# triac_driver.net
KiCad netlist of a schematic drawn in EAGLE
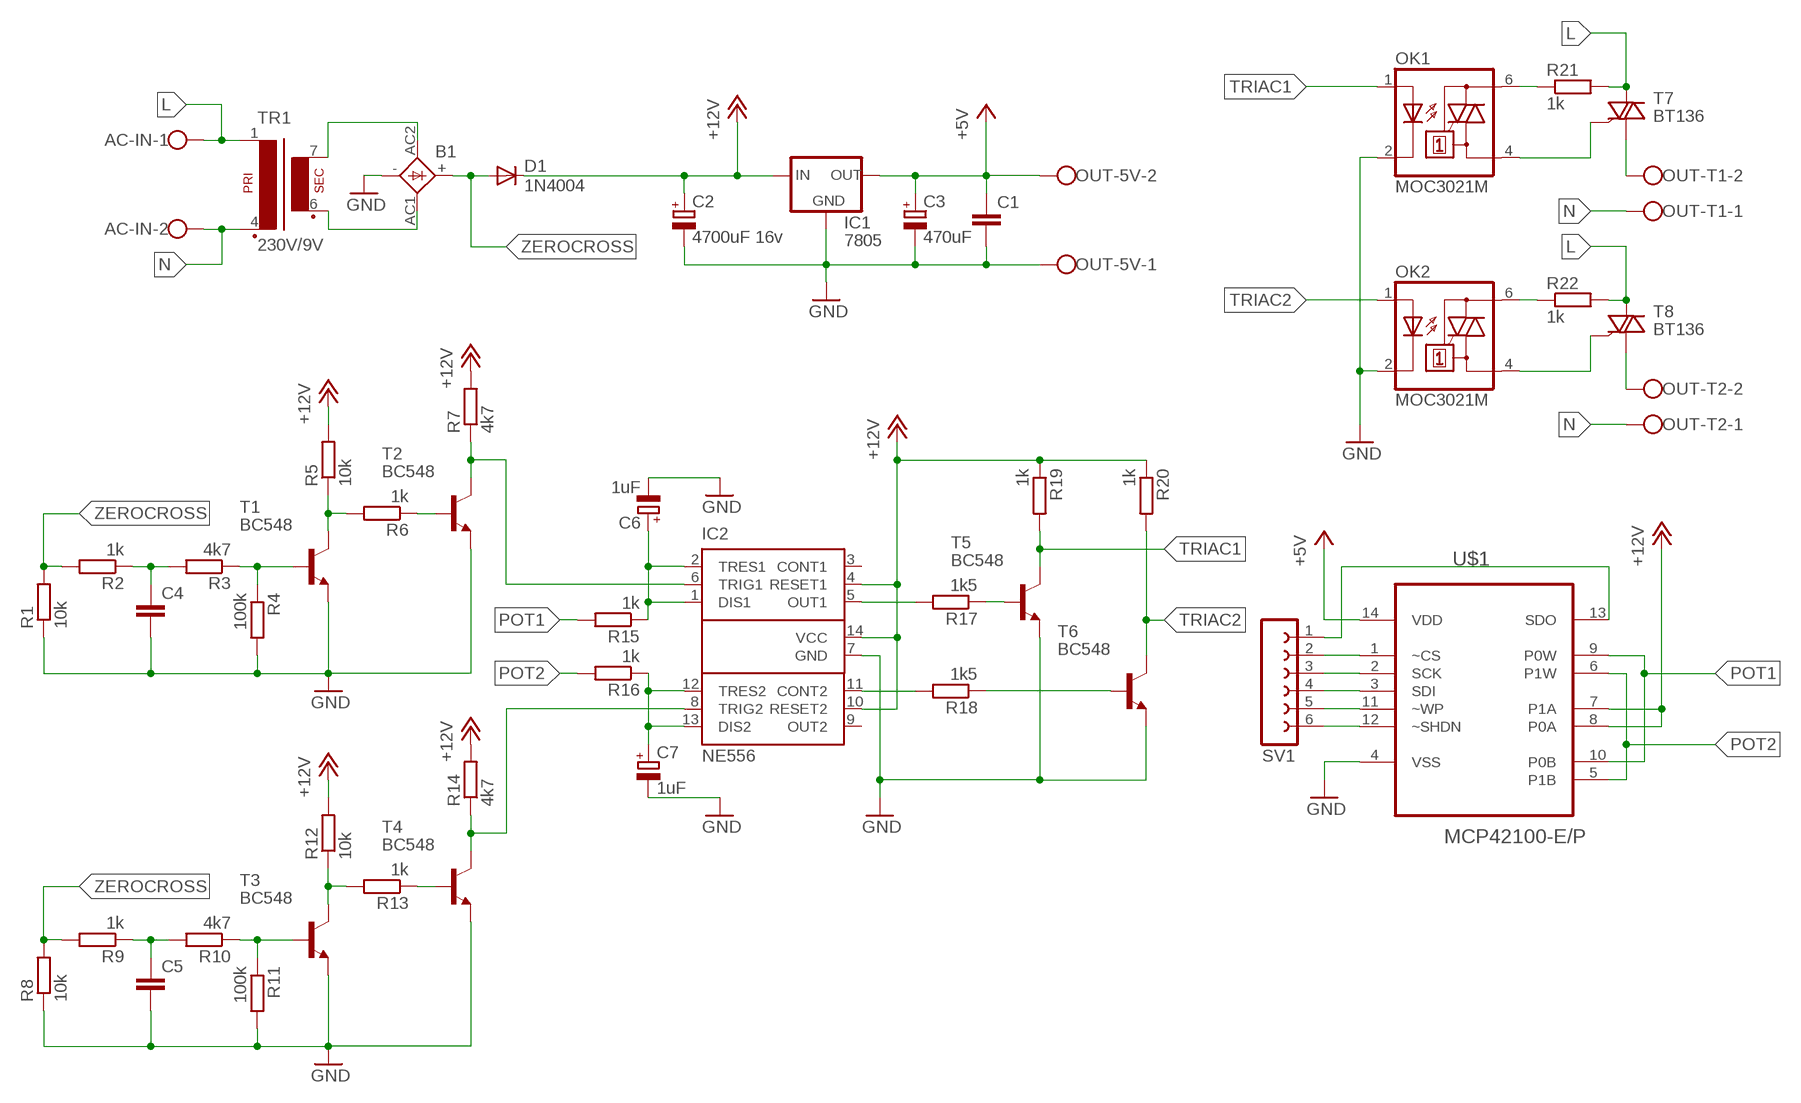
[diagram p0: schematic, sheet 1]

(export (version "E")
  (design (tool "Eeschema 10.0.6"))
  (components
    (comp (ref "AC-IN")
      (value "W237-102")
      (footprint "eagle-import:W237-102")
      (fields (field (name "MPN") "237-102"))
      (libsource (lib "eagle-import") (part "W237-102"))
    )
    (comp (ref "B1")
      (value "FBP1,5")
      (footprint "eagle-import:FBP1,5")
      (libsource (lib "eagle-import") (part "FBP1,5"))
    )
    (comp (ref "C1")
      (value "C-EU025-060X050")
      (footprint "eagle-import:C025-060X050")
      (libsource (lib "eagle-import") (part "C-EU025-060X050"))
    )
    (comp (ref "C2")
      (value "4700uF 16v")
      (footprint "eagle-import:E3,5-8")
      (libsource (lib "eagle-import") (part "CPOL-EUE3.5-8"))
    )
    (comp (ref "C3")
      (value "470uF")
      (footprint "eagle-import:E3,5-8")
      (libsource (lib "eagle-import") (part "CPOL-EUE3.5-8"))
    )
    (comp (ref "C4")
      (value "C-EU025-060X050")
      (footprint "eagle-import:C025-060X050")
      (libsource (lib "eagle-import") (part "C-EU025-060X050"))
    )
    (comp (ref "C5")
      (value "C-EU025-060X050")
      (footprint "eagle-import:C025-060X050")
      (libsource (lib "eagle-import") (part "C-EU025-060X050"))
    )
    (comp (ref "C6")
      (value "1uF")
      (footprint "eagle-import:E3,5-8")
      (libsource (lib "eagle-import") (part "CPOL-EUE3.5-8"))
    )
    (comp (ref "C7")
      (value "1uF")
      (footprint "eagle-import:E3,5-8")
      (libsource (lib "eagle-import") (part "CPOL-EUE3.5-8"))
    )
    (comp (ref "D1")
      (value "1N4004")
      (footprint "eagle-import:DO41-10")
      (libsource (lib "eagle-import") (part "1N4004"))
    )
    (comp (ref "IC1")
      (value "7805")
      (footprint "eagle-import:78LXX")
      (libsource (lib "eagle-import") (part "78LXX"))
    )
    (comp (ref "IC2")
      (value "NE556")
      (footprint "eagle-import:DIL14")
      (libsource (lib "eagle-import") (part "NE556"))
    )
    (comp (ref "OK1")
      (value "MOC3021M")
      (footprint "eagle-import:DIL06")
      (fields (field (name "MF") "FAIRCHILD SEMICONDUCTOR") (field (name "MPN") "MOC3021-M"))
      (libsource (lib "eagle-import") (part "MOC30M21"))
    )
    (comp (ref "OK2")
      (value "MOC3021M")
      (footprint "eagle-import:DIL06")
      (fields (field (name "MF") "FAIRCHILD SEMICONDUCTOR") (field (name "MPN") "MOC3021-M"))
      (libsource (lib "eagle-import") (part "MOC30M21"))
    )
    (comp (ref "OUT-5V")
      (value "W237-102")
      (footprint "eagle-import:W237-102")
      (fields (field (name "MPN") "237-102"))
      (libsource (lib "eagle-import") (part "W237-102"))
    )
    (comp (ref "OUT-T1")
      (value "W237-102")
      (footprint "eagle-import:W237-102")
      (fields (field (name "MPN") "237-102"))
      (libsource (lib "eagle-import") (part "W237-102"))
    )
    (comp (ref "OUT-T2")
      (value "W237-102")
      (footprint "eagle-import:W237-102")
      (fields (field (name "MPN") "237-102"))
      (libsource (lib "eagle-import") (part "W237-102"))
    )
    (comp (ref "R1")
      (value "10k")
      (footprint "eagle-import:0204_7")
      (libsource (lib "eagle-import") (part "R-EU_0204/7"))
    )
    (comp (ref "R2")
      (value "1k")
      (footprint "eagle-import:0204_7")
      (libsource (lib "eagle-import") (part "R-EU_0204/7"))
    )
    (comp (ref "R3")
      (value "4k7")
      (footprint "eagle-import:0204_7")
      (libsource (lib "eagle-import") (part "R-EU_0204/7"))
    )
    (comp (ref "R4")
      (value "100k")
      (footprint "eagle-import:0204_7")
      (libsource (lib "eagle-import") (part "R-EU_0204/7"))
    )
    (comp (ref "R5")
      (value "10k")
      (footprint "eagle-import:0204_7")
      (libsource (lib "eagle-import") (part "R-EU_0204/7"))
    )
    (comp (ref "R6")
      (value "1k")
      (footprint "eagle-import:0204_7")
      (libsource (lib "eagle-import") (part "R-EU_0204/7"))
    )
    (comp (ref "R7")
      (value "4k7")
      (footprint "eagle-import:0204_7")
      (libsource (lib "eagle-import") (part "R-EU_0204/7"))
    )
    (comp (ref "R8")
      (value "10k")
      (footprint "eagle-import:0204_7")
      (libsource (lib "eagle-import") (part "R-EU_0204/7"))
    )
    (comp (ref "R9")
      (value "1k")
      (footprint "eagle-import:0204_7")
      (libsource (lib "eagle-import") (part "R-EU_0204/7"))
    )
    (comp (ref "R10")
      (value "4k7")
      (footprint "eagle-import:0204_7")
      (libsource (lib "eagle-import") (part "R-EU_0204/7"))
    )
    (comp (ref "R11")
      (value "100k")
      (footprint "eagle-import:0204_7")
      (libsource (lib "eagle-import") (part "R-EU_0204/7"))
    )
    (comp (ref "R12")
      (value "10k")
      (footprint "eagle-import:0204_7")
      (libsource (lib "eagle-import") (part "R-EU_0204/7"))
    )
    (comp (ref "R13")
      (value "1k")
      (footprint "eagle-import:0204_7")
      (libsource (lib "eagle-import") (part "R-EU_0204/7"))
    )
    (comp (ref "R14")
      (value "4k7")
      (footprint "eagle-import:0204_7")
      (libsource (lib "eagle-import") (part "R-EU_0204/7"))
    )
    (comp (ref "R15")
      (value "1k")
      (footprint "eagle-import:0204_7")
      (libsource (lib "eagle-import") (part "R-EU_0204/7"))
    )
    (comp (ref "R16")
      (value "1k")
      (footprint "eagle-import:0204_7")
      (libsource (lib "eagle-import") (part "R-EU_0204/7"))
    )
    (comp (ref "R17")
      (value "1k5")
      (footprint "eagle-import:0204_7")
      (libsource (lib "eagle-import") (part "R-EU_0204/7"))
    )
    (comp (ref "R18")
      (value "1k5")
      (footprint "eagle-import:0204_7")
      (libsource (lib "eagle-import") (part "R-EU_0204/7"))
    )
    (comp (ref "R19")
      (value "1k")
      (footprint "eagle-import:0204_7")
      (libsource (lib "eagle-import") (part "R-EU_0204/7"))
    )
    (comp (ref "R20")
      (value "1k")
      (footprint "eagle-import:0204_7")
      (libsource (lib "eagle-import") (part "R-EU_0204/7"))
    )
    (comp (ref "R21")
      (value "1k")
      (footprint "eagle-import:0204_7")
      (libsource (lib "eagle-import") (part "R-EU_0204/7"))
    )
    (comp (ref "R22")
      (value "1k")
      (footprint "eagle-import:0204_7")
      (libsource (lib "eagle-import") (part "R-EU_0204/7"))
    )
    (comp (ref "SV1")
      (value "FE06-1")
      (footprint "eagle-import:FE06")
      (libsource (lib "eagle-import") (part "FE06-1"))
    )
    (comp (ref "T1")
      (value "BC548")
      (footprint "eagle-import:TO92")
      (libsource (lib "eagle-import") (part "BC547"))
    )
    (comp (ref "T2")
      (value "BC548")
      (footprint "eagle-import:TO92")
      (libsource (lib "eagle-import") (part "BC547"))
    )
    (comp (ref "T3")
      (value "BC548")
      (footprint "eagle-import:TO92")
      (libsource (lib "eagle-import") (part "BC547"))
    )
    (comp (ref "T4")
      (value "BC548")
      (footprint "eagle-import:TO92")
      (libsource (lib "eagle-import") (part "BC547"))
    )
    (comp (ref "T5")
      (value "BC548")
      (footprint "eagle-import:TO92")
      (libsource (lib "eagle-import") (part "BC547"))
    )
    (comp (ref "T6")
      (value "BC548")
      (footprint "eagle-import:TO92")
      (libsource (lib "eagle-import") (part "BC547"))
    )
    (comp (ref "T7")
      (value "BT136")
      (footprint "eagle-import:TO220AB")
      (libsource (lib "eagle-import") (part "BT136"))
    )
    (comp (ref "T8")
      (value "BT136")
      (footprint "eagle-import:TO220AB")
      (libsource (lib "eagle-import") (part "BT136"))
    )
    (comp (ref "TR1")
      (value "230V/9V")
      (footprint "eagle-import:EE20-1")
      (libsource (lib "eagle-import") (part "EE20-1"))
    )
    (comp (ref "U$1")
      (value "MCP42100-E/P")
      (footprint "eagle-import:DIP254P762X533-14")
      (fields (field (name "MPN") "MCP4241-103E/P"))
      (libsource (lib "eagle-import") (part "MCP4241-103E/P"))
    )
  )
  (nets
    (net (code "1") (name "+5V") (class "Default")
      (node (ref "C1") (pin "1") (pinfunction "1_1") (pintype "passive"))
      (node (ref "C3") (pin "+") (pinfunction "+_+") (pintype "passive"))
      (node (ref "IC1") (pin "OUT") (pinfunction "OUT_OUT") (pintype "passive"))
      (node (ref "OUT-5V") (pin "2") (pinfunction "KL_2") (pintype "passive"))
      (node (ref "U$1") (pin "14") (pinfunction "VDD_14") (pintype "power_in"))
    )
    (net (code "2") (name "+12V") (class "Default")
      (node (ref "C2") (pin "+") (pinfunction "+_+") (pintype "passive"))
      (node (ref "D1") (pin "C") (pinfunction "C_C") (pintype "passive"))
      (node (ref "IC1") (pin "IN") (pinfunction "IN_IN") (pintype "input"))
      (node (ref "IC2") (pin "10") (pinfunction "RESET2_10") (pintype "input"))
      (node (ref "IC2") (pin "14") (pinfunction "VCC_14") (pintype "power_in"))
      (node (ref "IC2") (pin "4") (pinfunction "RESET1_4") (pintype "input"))
      (node (ref "R12") (pin "2") (pinfunction "2_2") (pintype "passive"))
      (node (ref "R14") (pin "2") (pinfunction "2_2") (pintype "passive"))
      (node (ref "R19") (pin "1") (pinfunction "1_1") (pintype "passive"))
      (node (ref "R20") (pin "1") (pinfunction "1_1") (pintype "passive"))
      (node (ref "R5") (pin "2") (pinfunction "2_2") (pintype "passive"))
      (node (ref "R7") (pin "2") (pinfunction "2_2") (pintype "passive"))
      (node (ref "U$1") (pin "7") (pinfunction "P1A_7") (pintype "bidirectional"))
      (node (ref "U$1") (pin "8") (pinfunction "P0A_8") (pintype "bidirectional"))
    )
    (net (code "3") (name "GND") (class "Default")
      (node (ref "B1") (pin "-") (pinfunction "-_-") (pintype "passive"))
      (node (ref "C1") (pin "2") (pinfunction "2_2") (pintype "passive"))
      (node (ref "C2") (pin "-") (pinfunction "-_-") (pintype "passive"))
      (node (ref "C3") (pin "-") (pinfunction "-_-") (pintype "passive"))
      (node (ref "C4") (pin "2") (pinfunction "2_2") (pintype "passive"))
      (node (ref "C5") (pin "2") (pinfunction "2_2") (pintype "passive"))
      (node (ref "C6") (pin "-") (pinfunction "-_-") (pintype "passive"))
      (node (ref "C7") (pin "-") (pinfunction "-_-") (pintype "passive"))
      (node (ref "IC1") (pin "GND") (pinfunction "GND_GND") (pintype "input"))
      (node (ref "IC2") (pin "7") (pinfunction "GND_7") (pintype "power_in"))
      (node (ref "OK1") (pin "2") (pinfunction "C_2") (pintype "passive"))
      (node (ref "OK2") (pin "2") (pinfunction "C_2") (pintype "passive"))
      (node (ref "OUT-5V") (pin "1") (pinfunction "KL_1") (pintype "passive"))
      (node (ref "R1") (pin "1") (pinfunction "1_1") (pintype "passive"))
      (node (ref "R11") (pin "2") (pinfunction "2_2") (pintype "passive"))
      (node (ref "R4") (pin "2") (pinfunction "2_2") (pintype "passive"))
      (node (ref "R8") (pin "1") (pinfunction "1_1") (pintype "passive"))
      (node (ref "T1") (pin "1") (pinfunction "E_1") (pintype "passive"))
      (node (ref "T2") (pin "1") (pinfunction "E_1") (pintype "passive"))
      (node (ref "T3") (pin "1") (pinfunction "E_1") (pintype "passive"))
      (node (ref "T4") (pin "1") (pinfunction "E_1") (pintype "passive"))
      (node (ref "T5") (pin "1") (pinfunction "E_1") (pintype "passive"))
      (node (ref "T6") (pin "1") (pinfunction "E_1") (pintype "passive"))
      (node (ref "U$1") (pin "4") (pinfunction "VSS_4") (pintype "power_in"))
    )
    (net (code "4") (name "L") (class "Default")
      (node (ref "AC-IN") (pin "1") (pinfunction "KL_1") (pintype "passive"))
      (node (ref "R21") (pin "2") (pinfunction "2_2") (pintype "passive"))
      (node (ref "R22") (pin "2") (pinfunction "2_2") (pintype "passive"))
      (node (ref "T7") (pin "2") (pinfunction "A2_2") (pintype "passive"))
      (node (ref "T8") (pin "2") (pinfunction "A2_2") (pintype "passive"))
      (node (ref "TR1") (pin "1") (pinfunction "P1_1") (pintype "passive"))
    )
    (net (code "5") (name "N") (class "Default")
      (node (ref "AC-IN") (pin "2") (pinfunction "KL_2") (pintype "passive"))
      (node (ref "OUT-T1") (pin "1") (pinfunction "KL_1") (pintype "passive"))
      (node (ref "OUT-T2") (pin "1") (pinfunction "KL_1") (pintype "passive"))
      (node (ref "TR1") (pin "4") (pinfunction "P2_4") (pintype "passive"))
    )
    (net (code "6") (name "Net-(B1-AC1)") (class "Default")
      (node (ref "B1") (pin "AC2") (pinfunction "AC1_AC2") (pintype "passive"))
      (node (ref "TR1") (pin "7") (pinfunction "S4_7") (pintype "passive"))
    )
    (net (code "7") (name "Net-(B1-AC2)") (class "Default")
      (node (ref "B1") (pin "AC1") (pinfunction "AC2_AC1") (pintype "passive"))
      (node (ref "TR1") (pin "6") (pinfunction "S3_6") (pintype "passive"))
    )
    (net (code "8") (name "Net-(C4-Pad1)") (class "Default")
      (node (ref "C4") (pin "1") (pinfunction "1_1") (pintype "passive"))
      (node (ref "R2") (pin "1") (pinfunction "1_1") (pintype "passive"))
      (node (ref "R3") (pin "2") (pinfunction "2_2") (pintype "passive"))
    )
    (net (code "9") (name "Net-(C5-Pad1)") (class "Default")
      (node (ref "C5") (pin "1") (pinfunction "1_1") (pintype "passive"))
      (node (ref "R10") (pin "2") (pinfunction "2_2") (pintype "passive"))
      (node (ref "R9") (pin "1") (pinfunction "1_1") (pintype "passive"))
    )
    (net (code "10") (name "Net-(IC2-CONT2)") (class "Default")
      (node (ref "IC2") (pin "11") (pinfunction "CONT2_11") (pintype "input"))
      (node (ref "R18") (pin "2") (pinfunction "2_2") (pintype "passive"))
    )
    (net (code "11") (name "Net-(IC2-DIS1)") (class "Default")
      (node (ref "C6") (pin "+") (pinfunction "+_+") (pintype "passive"))
      (node (ref "IC2") (pin "1") (pinfunction "DIS1_1") (pintype "input"))
      (node (ref "IC2") (pin "2") (pinfunction "TRES1_2") (pintype "input"))
      (node (ref "R15") (pin "1") (pinfunction "1_1") (pintype "passive"))
    )
    (net (code "12") (name "Net-(IC2-DIS2)") (class "Default")
      (node (ref "C7") (pin "+") (pinfunction "+_+") (pintype "passive"))
      (node (ref "IC2") (pin "12") (pinfunction "TRES2_12") (pintype "input"))
      (node (ref "IC2") (pin "13") (pinfunction "DIS2_13") (pintype "input"))
      (node (ref "R16") (pin "1") (pinfunction "1_1") (pintype "passive"))
    )
    (net (code "13") (name "Net-(IC2-OUT1)") (class "Default")
      (node (ref "IC2") (pin "5") (pinfunction "OUT1_5") (pintype "output"))
      (node (ref "R17") (pin "2") (pinfunction "2_2") (pintype "passive"))
    )
    (net (code "14") (name "Net-(IC2-TRIG1)") (class "Default")
      (node (ref "IC2") (pin "6") (pinfunction "TRIG1_6") (pintype "input"))
      (node (ref "R7") (pin "1") (pinfunction "1_1") (pintype "passive"))
      (node (ref "T2") (pin "3") (pinfunction "C_3") (pintype "passive"))
    )
    (net (code "15") (name "Net-(IC2-TRIG2)") (class "Default")
      (node (ref "IC2") (pin "8") (pinfunction "TRIG2_8") (pintype "input"))
      (node (ref "R14") (pin "1") (pinfunction "1_1") (pintype "passive"))
      (node (ref "T4") (pin "3") (pinfunction "C_3") (pintype "passive"))
    )
    (net (code "16") (name "Net-(OK1-A1)") (class "Default")
      (node (ref "OK1") (pin "4") (pinfunction "A1_4") (pintype "passive"))
      (node (ref "T7") (pin "3") (pinfunction "G_3") (pintype "passive"))
    )
    (net (code "17") (name "Net-(OK1-A2)") (class "Default")
      (node (ref "OK1") (pin "6") (pinfunction "A2_6") (pintype "passive"))
      (node (ref "R21") (pin "1") (pinfunction "1_1") (pintype "passive"))
    )
    (net (code "18") (name "Net-(OK2-A1)") (class "Default")
      (node (ref "OK2") (pin "4") (pinfunction "A1_4") (pintype "passive"))
      (node (ref "T8") (pin "3") (pinfunction "G_3") (pintype "passive"))
    )
    (net (code "19") (name "Net-(OK2-A2)") (class "Default")
      (node (ref "OK2") (pin "6") (pinfunction "A2_6") (pintype "passive"))
      (node (ref "R22") (pin "1") (pinfunction "1_1") (pintype "passive"))
    )
    (net (code "20") (name "Net-(OUT-T1B-KL)") (class "Default")
      (node (ref "OUT-T1") (pin "2") (pinfunction "KL_2") (pintype "passive"))
      (node (ref "T7") (pin "1") (pinfunction "A1_1") (pintype "passive"))
    )
    (net (code "21") (name "Net-(OUT-T2B-KL)") (class "Default")
      (node (ref "OUT-T2") (pin "2") (pinfunction "KL_2") (pintype "passive"))
      (node (ref "T8") (pin "1") (pinfunction "A1_1") (pintype "passive"))
    )
    (net (code "22") (name "Net-(T1-B)") (class "Default")
      (node (ref "R3") (pin "1") (pinfunction "1_1") (pintype "passive"))
      (node (ref "R4") (pin "1") (pinfunction "1_1") (pintype "passive"))
      (node (ref "T1") (pin "2") (pinfunction "B_2") (pintype "passive"))
    )
    (net (code "23") (name "Net-(T1-C)") (class "Default")
      (node (ref "R5") (pin "1") (pinfunction "1_1") (pintype "passive"))
      (node (ref "R6") (pin "2") (pinfunction "2_2") (pintype "passive"))
      (node (ref "T1") (pin "3") (pinfunction "C_3") (pintype "passive"))
    )
    (net (code "24") (name "Net-(T2-B)") (class "Default")
      (node (ref "R6") (pin "1") (pinfunction "1_1") (pintype "passive"))
      (node (ref "T2") (pin "2") (pinfunction "B_2") (pintype "passive"))
    )
    (net (code "25") (name "Net-(T3-B)") (class "Default")
      (node (ref "R10") (pin "1") (pinfunction "1_1") (pintype "passive"))
      (node (ref "R11") (pin "1") (pinfunction "1_1") (pintype "passive"))
      (node (ref "T3") (pin "2") (pinfunction "B_2") (pintype "passive"))
    )
    (net (code "26") (name "Net-(T3-C)") (class "Default")
      (node (ref "R12") (pin "1") (pinfunction "1_1") (pintype "passive"))
      (node (ref "R13") (pin "2") (pinfunction "2_2") (pintype "passive"))
      (node (ref "T3") (pin "3") (pinfunction "C_3") (pintype "passive"))
    )
    (net (code "27") (name "Net-(T4-B)") (class "Default")
      (node (ref "R13") (pin "1") (pinfunction "1_1") (pintype "passive"))
      (node (ref "T4") (pin "2") (pinfunction "B_2") (pintype "passive"))
    )
    (net (code "28") (name "Net-(T5-B)") (class "Default")
      (node (ref "R17") (pin "1") (pinfunction "1_1") (pintype "passive"))
      (node (ref "T5") (pin "2") (pinfunction "B_2") (pintype "passive"))
    )
    (net (code "29") (name "Net-(T6-B)") (class "Default")
      (node (ref "R18") (pin "1") (pinfunction "1_1") (pintype "passive"))
      (node (ref "T6") (pin "2") (pinfunction "B_2") (pintype "passive"))
    )
    (net (code "30") (name "Net-(U$1-SCK)") (class "Default")
      (node (ref "SV1") (pin "3") (pinfunction "3_3") (pintype "passive"))
      (node (ref "U$1") (pin "2") (pinfunction "SCK_2") (pintype "input"))
    )
    (net (code "31") (name "Net-(U$1-SDI)") (class "Default")
      (node (ref "SV1") (pin "4") (pinfunction "4_4") (pintype "passive"))
      (node (ref "U$1") (pin "3") (pinfunction "SDI_3") (pintype "input"))
    )
    (net (code "32") (name "Net-(U$1-SDO)") (class "Default")
      (node (ref "SV1") (pin "1") (pinfunction "1_1") (pintype "passive"))
      (node (ref "U$1") (pin "13") (pinfunction "SDO_13") (pintype "output"))
    )
    (net (code "33") (name "Net-(U$1-~{CS})") (class "Default")
      (node (ref "SV1") (pin "2") (pinfunction "2_2") (pintype "passive"))
      (node (ref "U$1") (pin "1") (pinfunction "~{CS}_1") (pintype "input"))
    )
    (net (code "34") (name "Net-(U$1-~{SHDN})") (class "Default")
      (node (ref "SV1") (pin "6") (pinfunction "6_6") (pintype "passive"))
      (node (ref "U$1") (pin "12") (pinfunction "~{SHDN}_12") (pintype "input"))
    )
    (net (code "35") (name "Net-(U$1-~{WP})") (class "Default")
      (node (ref "SV1") (pin "5") (pinfunction "5_5") (pintype "passive"))
      (node (ref "U$1") (pin "11") (pinfunction "~{WP}_11") (pintype "input"))
    )
    (net (code "36") (name "POT1") (class "Default")
      (node (ref "R15") (pin "2") (pinfunction "2_2") (pintype "passive"))
      (node (ref "U$1") (pin "10") (pinfunction "P0B_10") (pintype "bidirectional"))
      (node (ref "U$1") (pin "9") (pinfunction "P0W_9") (pintype "bidirectional"))
    )
    (net (code "37") (name "POT2") (class "Default")
      (node (ref "R16") (pin "2") (pinfunction "2_2") (pintype "passive"))
      (node (ref "U$1") (pin "5") (pinfunction "P1B_5") (pintype "bidirectional"))
      (node (ref "U$1") (pin "6") (pinfunction "P1W_6") (pintype "bidirectional"))
    )
    (net (code "38") (name "TRIAC1") (class "Default")
      (node (ref "OK1") (pin "1") (pinfunction "A_1") (pintype "passive"))
      (node (ref "R19") (pin "2") (pinfunction "2_2") (pintype "passive"))
      (node (ref "T5") (pin "3") (pinfunction "C_3") (pintype "passive"))
    )
    (net (code "39") (name "TRIAC2") (class "Default")
      (node (ref "OK2") (pin "1") (pinfunction "A_1") (pintype "passive"))
      (node (ref "R20") (pin "2") (pinfunction "2_2") (pintype "passive"))
      (node (ref "T6") (pin "3") (pinfunction "C_3") (pintype "passive"))
    )
    (net (code "40") (name "ZEROCROSS") (class "Default")
      (node (ref "B1") (pin "+") (pinfunction "+_+") (pintype "passive"))
      (node (ref "D1") (pin "A") (pinfunction "A_A") (pintype "passive"))
      (node (ref "R1") (pin "2") (pinfunction "2_2") (pintype "passive"))
      (node (ref "R2") (pin "2") (pinfunction "2_2") (pintype "passive"))
      (node (ref "R8") (pin "2") (pinfunction "2_2") (pintype "passive"))
      (node (ref "R9") (pin "2") (pinfunction "2_2") (pintype "passive"))
    )
    (net (code "41") (name "unconnected-(IC2-CONT1-Pad3)") (class "Default")
      (node (ref "IC2") (pin "3") (pinfunction "CONT1_3") (pintype "input"))
    )
    (net (code "42") (name "unconnected-(IC2-OUT2-Pad9)") (class "Default")
      (node (ref "IC2") (pin "9") (pinfunction "OUT2_9") (pintype "output"))
    )
  )
)
